# FMC_connector.net
KiCad netlist of a schematic drawn in Altium Designer
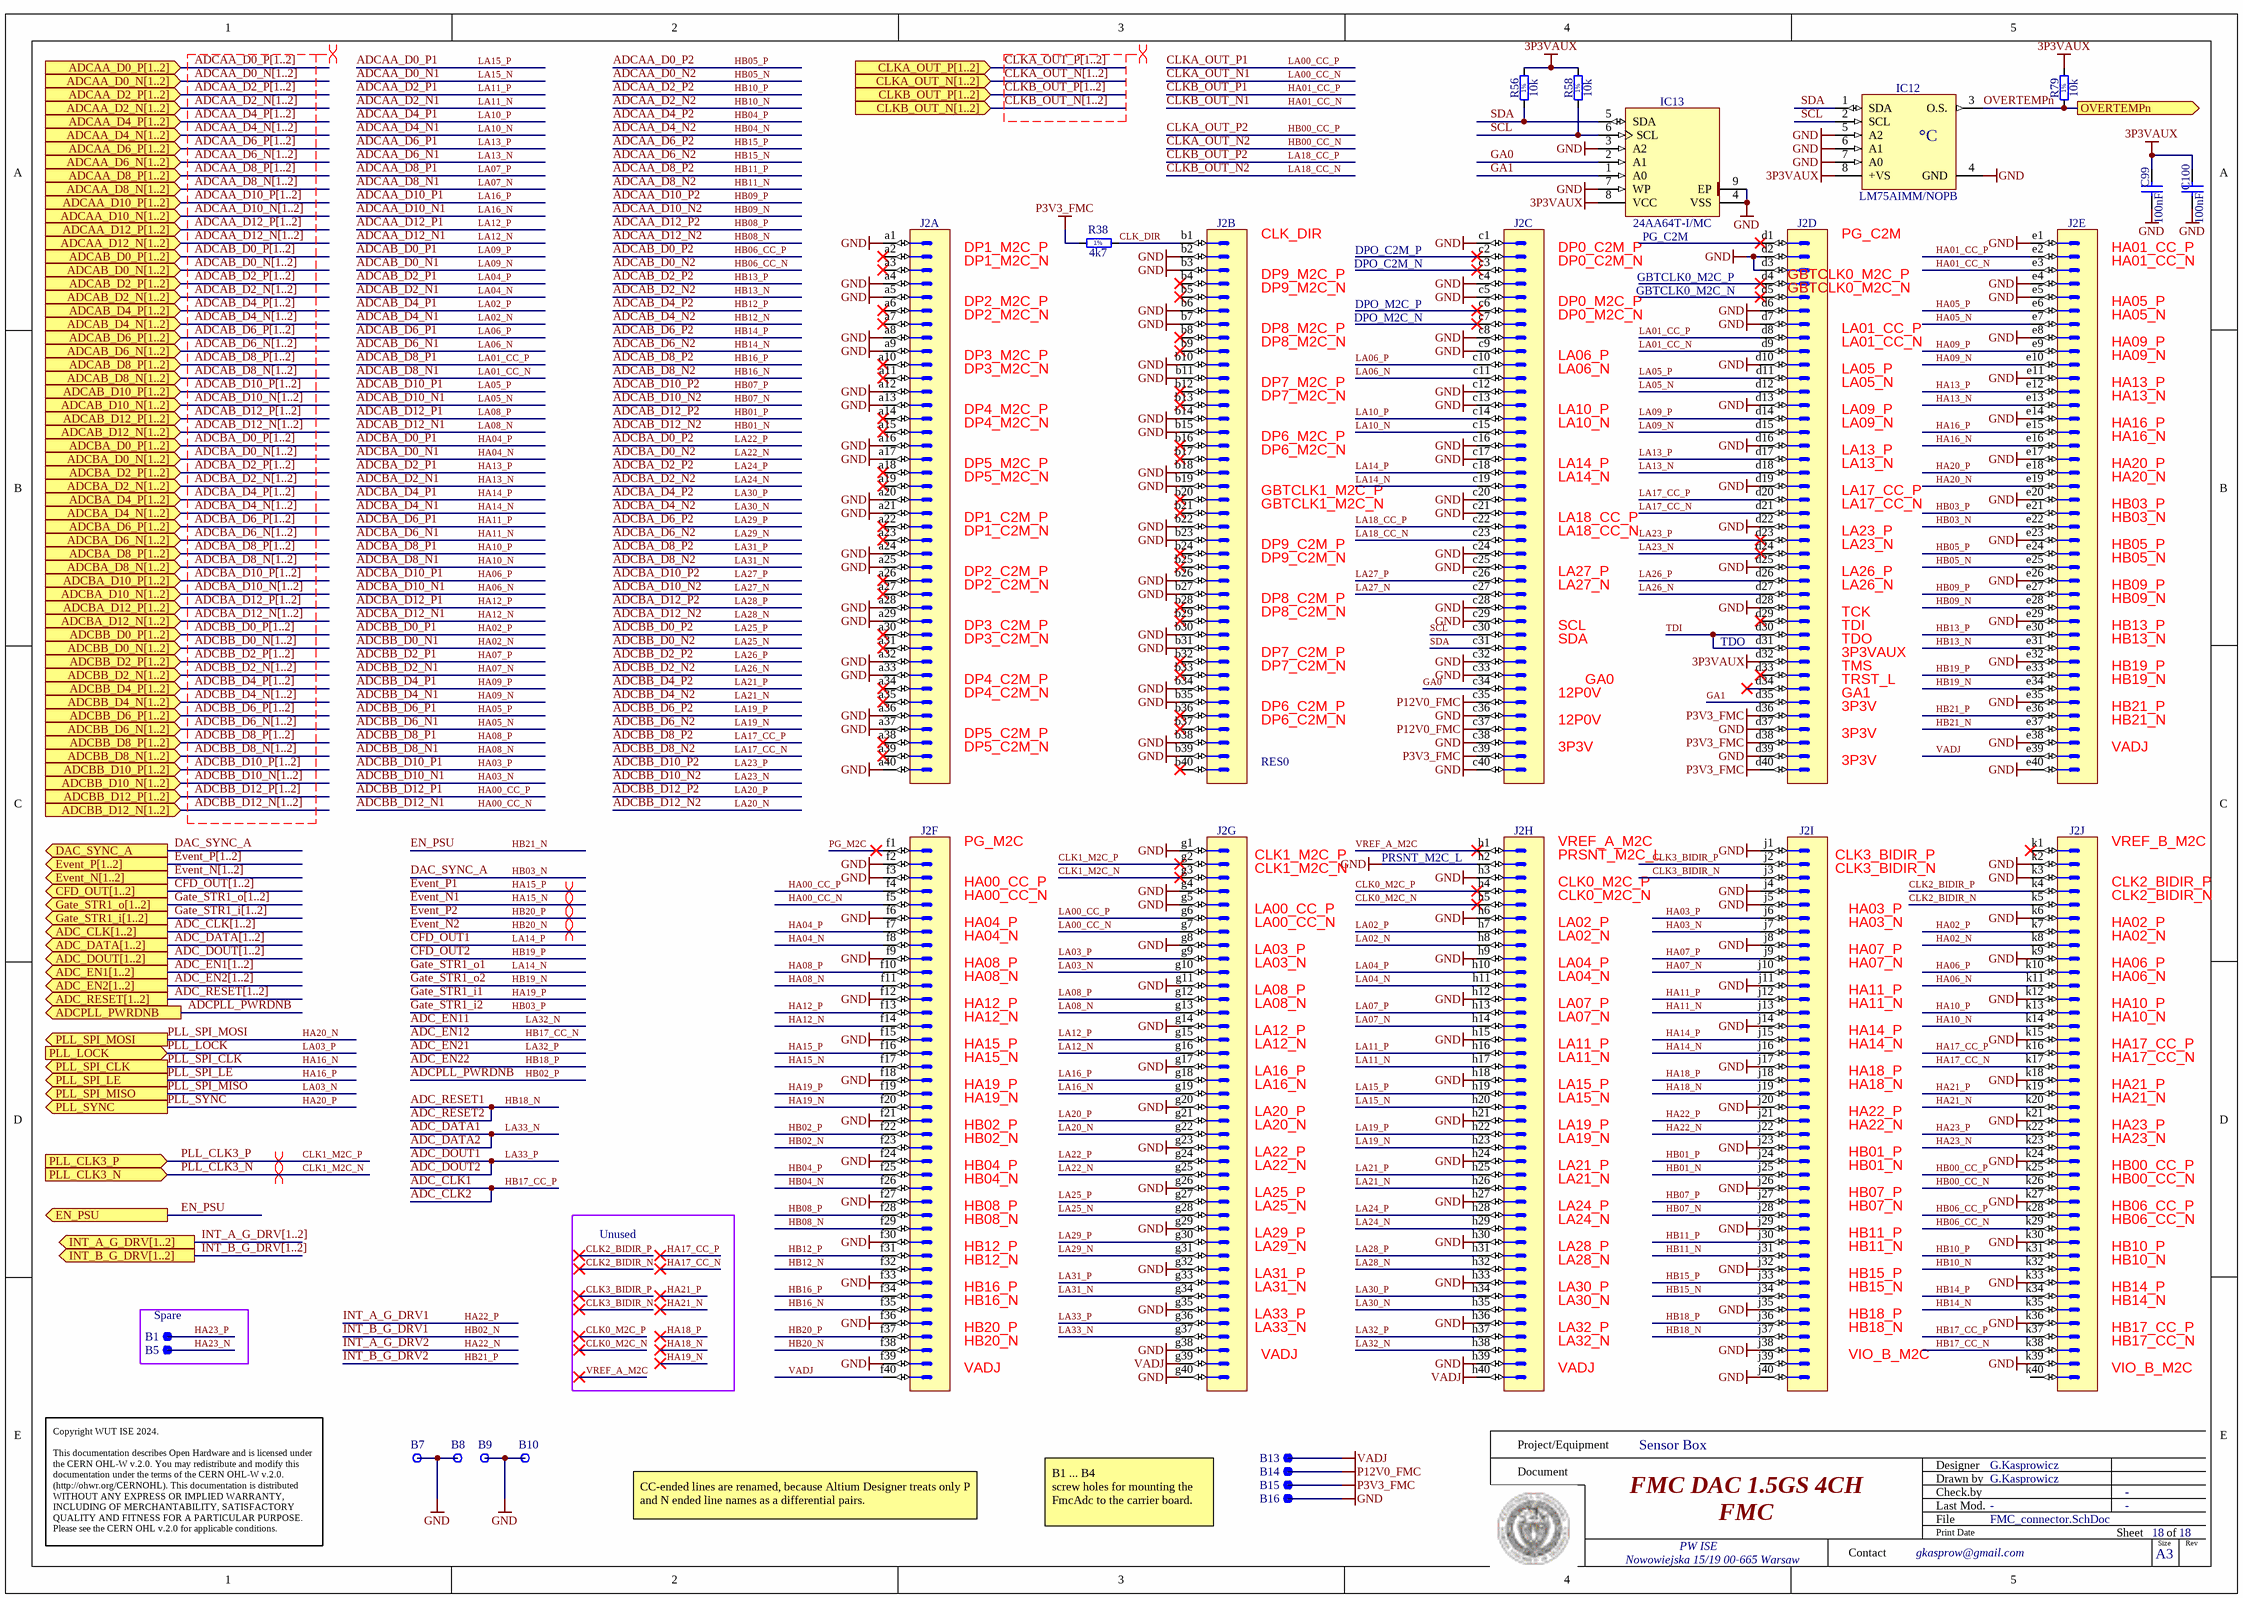
[diagram p0: FMC_connector.SchDoc]

(export (version "E")
  (design (tool "Eeschema 10.0.6"))
  (components
    (comp (ref "B1")
      (value "SMD Pad")
      (footprint "C100")
      (description "Pad")
      (fields (field (name "PART NUMBER") "SMD_PAD_D1MM") (field (name "AUTHOR") "CERN DEM JLC"))
      (libsource (lib "Eletro-mechanical") (part "Single SMD Pad (Round)"))
    )
    (comp (ref "B5")
      (value "SMD Pad")
      (footprint "C100")
      (description "Pad")
      (fields (field (name "PART NUMBER") "SMD_PAD_D1MM") (field (name "AUTHOR") "CERN DEM JLC"))
      (libsource (lib "Eletro-mechanical") (part "Single SMD Pad (Round)"))
    )
    (comp (ref "B7")
      (value "Plated Hole")
      (footprint "MTG300_600")
      (description "Single Terminal Socket")
      (fields (field (name "PART NUMBER") "PLATED_HOLE3.0_PAD6.0") (field (name "AUTHOR") "CERN DEM JLC"))
      (libsource (lib "Eletro-mechanical") (part "Single Terminal Socket"))
    )
    (comp (ref "B8")
      (value "Plated Hole")
      (footprint "MTG300_600")
      (description "Single Terminal Socket")
      (fields (field (name "PART NUMBER") "PLATED_HOLE3.0_PAD6.0") (field (name "AUTHOR") "CERN DEM JLC"))
      (libsource (lib "Eletro-mechanical") (part "Single Terminal Socket"))
    )
    (comp (ref "B9")
      (value "Plated Hole")
      (footprint "MTG300_600")
      (description "Single Terminal Socket")
      (fields (field (name "PART NUMBER") "PLATED_HOLE3.0_PAD6.0") (field (name "AUTHOR") "CERN DEM JLC"))
      (libsource (lib "Eletro-mechanical") (part "Single Terminal Socket"))
    )
    (comp (ref "B10")
      (value "Plated Hole")
      (footprint "MTG300_600")
      (description "Single Terminal Socket")
      (fields (field (name "PART NUMBER") "PLATED_HOLE3.0_PAD6.0") (field (name "AUTHOR") "CERN DEM JLC"))
      (libsource (lib "Eletro-mechanical") (part "Single Terminal Socket"))
    )
    (comp (ref "B13")
      (value "SMD Pad")
      (footprint "C100")
      (description "Pad")
      (fields (field (name "PART NUMBER") "SMD_PAD_D1MM") (field (name "AUTHOR") "CERN DEM JLC"))
      (libsource (lib "Eletro-mechanical") (part "Single SMD Pad (Round)"))
    )
    (comp (ref "B14")
      (value "SMD Pad")
      (footprint "C100")
      (description "Pad")
      (fields (field (name "PART NUMBER") "SMD_PAD_D1MM") (field (name "AUTHOR") "CERN DEM JLC"))
      (libsource (lib "Eletro-mechanical") (part "Single SMD Pad (Round)"))
    )
    (comp (ref "B15")
      (value "SMD Pad")
      (footprint "C100")
      (description "Pad")
      (fields (field (name "PART NUMBER") "SMD_PAD_D1MM") (field (name "AUTHOR") "CERN DEM JLC"))
      (libsource (lib "Eletro-mechanical") (part "Single SMD Pad (Round)"))
    )
    (comp (ref "B16")
      (value "SMD Pad")
      (footprint "C100")
      (description "Pad")
      (fields (field (name "PART NUMBER") "SMD_PAD_D1MM") (field (name "AUTHOR") "CERN DEM JLC"))
      (libsource (lib "Eletro-mechanical") (part "Single SMD Pad (Round)"))
    )
    (comp (ref "C99")
      (value "100nF")
      (footprint "CAPC1005X55N")
      (description "Non-polarised capacitor")
      (fields
        (field (name "PART NUMBER") "CC0402_100NF_16V_10%_X5R")
        (field (name "VOLTAGE") "16V")
        (field (name "AUTHOR") "CERN DEM JLC")
      )
      (libsource (lib "Capacitors") (part "Capacitor - non polarized"))
    )
    (comp (ref "C100")
      (value "100nF")
      (footprint "CAPC1005X55N")
      (description "Non-polarised capacitor")
      (fields
        (field (name "PART NUMBER") "CC0402_100NF_16V_10%_X5R")
        (field (name "VOLTAGE") "16V")
        (field (name "AUTHOR") "CERN DEM JLC")
      )
      (libsource (lib "Capacitors") (part "Capacitor - non polarized"))
    )
    (comp (ref "IC12")
      (value "LM75AIMM/NOPB")
      (footprint "SOP65P490X109-8N")
      (description "Digital Temperature Sensor and Thermal Watchdog with Two-Wire Interface")
      (fields (field (name "MANUFACTURER") "TEXAS INSTRUMENTS") (field (name "AUTHOR") "CERN DEM JLC"))
      (libsource (lib "ICs And Semiconductors") (part "LM75"))
    )
    (comp (ref "IC13")
      (value "24AA64T-I/MC")
      (footprint "SON50P300X200X100-9N-R175X155")
      (description "1.7V-5.5V 64K I2C Serial EEPROM")
      (fields (field (name "MANUFACTURER") "MICROCHIP TECHNOLOGY") (field (name "AUTHOR") "CERN DEM JLC"))
      (libsource (lib "ICs And Semiconductors") (part "24AA64T-I/MC"))
    )
    (comp (ref "J2")
      (value "VITA 57")
      (footprint "SAMTEC_ASP-134488-01")
      (description "Connector VITA 57, 400 Male contacts in 10 row abcdefghj")
      (fields
        (field (name "PART NUMBER") "SAMTEC_ASP-134488-01")
        (field (name "MANUFACTURER") "SAMTEC")
        (field (name "AUTHOR") "CERN DEM JLC")
      )
      (libsource (lib "Connectors") (part "Connector VITA 57 400 Male (abcdefghjk)"))
    )
    (comp (ref "R38")
      (value "4k7")
      (footprint "RESC1608X55N")
      (description "Resistor - 1%")
      (fields
        (field (name "PART NUMBER") "R0603_4K7_1%_0.1W_100PPM")
        (field (name "POWER") "0.1W")
        (field (name "AUTHOR") "CERN DEM JLC")
      )
      (libsource (lib "Resistors") (part "Resistor - 1%"))
    )
    (comp (ref "R56")
      (value "10k")
      (footprint "RESC1005X40N")
      (description "Resistor - 1%")
      (fields
        (field (name "PART NUMBER") "R0402_10K_1%_0.0625W_100PPM")
        (field (name "POWER") "0.0625W")
        (field (name "AUTHOR") "CERN DEM JLC")
      )
      (libsource (lib "Resistors") (part "Resistor - 1%"))
    )
    (comp (ref "R58")
      (value "10k")
      (footprint "RESC1005X40N")
      (description "Resistor - 1%")
      (fields
        (field (name "PART NUMBER") "R0402_10K_1%_0.0625W_100PPM")
        (field (name "POWER") "0.0625W")
        (field (name "AUTHOR") "CERN DEM JLC")
      )
      (libsource (lib "Resistors") (part "Resistor - 1%"))
    )
    (comp (ref "R79")
      (value "10k")
      (footprint "RESC1005X40N")
      (description "Resistor - 1%")
      (fields
        (field (name "PART NUMBER") "R0402_10K_1%_0.0625W_100PPM")
        (field (name "POWER") "0.0625W")
        (field (name "AUTHOR") "CERN DEM JLC")
      )
      (libsource (lib "Resistors") (part "Resistor - 1%"))
    )
  )
  (nets
    (net (code "1") (name "/ADCAA_D0_N1") (class "Default")
      (node (ref "J2") (pin "h20") (pinfunction "h20_h20") (pintype "bidirectional"))
    )
    (net (code "2") (name "/ADCAA_D0_N2") (class "Default")
      (node (ref "J2") (pin "e25") (pinfunction "e25_e25") (pintype "bidirectional"))
    )
    (net (code "4") (name "/ADCAA_D0_P1") (class "Default")
      (node (ref "J2") (pin "h19") (pinfunction "h19_h19") (pintype "bidirectional"))
    )
    (net (code "5") (name "/ADCAA_D0_P2") (class "Default")
      (node (ref "J2") (pin "e24") (pinfunction "e24_e24") (pintype "bidirectional"))
    )
    (net (code "7") (name "/ADCAA_D2_N1") (class "Default")
      (node (ref "J2") (pin "h17") (pinfunction "h17_h17") (pintype "bidirectional"))
    )
    (net (code "8") (name "/ADCAA_D2_N2") (class "Default")
      (node (ref "J2") (pin "k32") (pinfunction "k32_k32") (pintype "bidirectional"))
    )
    (net (code "10") (name "/ADCAA_D2_P1") (class "Default")
      (node (ref "J2") (pin "h16") (pinfunction "h16_h16") (pintype "bidirectional"))
    )
    (net (code "11") (name "/ADCAA_D2_P2") (class "Default")
      (node (ref "J2") (pin "k31") (pinfunction "k31_k31") (pintype "bidirectional"))
    )
    (net (code "13") (name "/ADCAA_D4_N1") (class "Default")
      (node (ref "J2") (pin "c15") (pinfunction "c15_c15") (pintype "bidirectional"))
    )
    (net (code "14") (name "/ADCAA_D4_N2") (class "Default")
      (node (ref "J2") (pin "f26") (pinfunction "f26_f26") (pintype "bidirectional"))
    )
    (net (code "16") (name "/ADCAA_D4_P1") (class "Default")
      (node (ref "J2") (pin "c14") (pinfunction "c14_c14") (pintype "bidirectional"))
    )
    (net (code "17") (name "/ADCAA_D4_P2") (class "Default")
      (node (ref "J2") (pin "f25") (pinfunction "f25_f25") (pintype "bidirectional"))
    )
    (net (code "19") (name "/ADCAA_D6_N1") (class "Default")
      (node (ref "J2") (pin "d18") (pinfunction "d18_d18") (pintype "bidirectional"))
    )
    (net (code "20") (name "/ADCAA_D6_N2") (class "Default")
      (node (ref "J2") (pin "j34") (pinfunction "j34_j34") (pintype "bidirectional"))
    )
    (net (code "22") (name "/ADCAA_D6_P1") (class "Default")
      (node (ref "J2") (pin "d17") (pinfunction "d17_d17") (pintype "bidirectional"))
    )
    (net (code "23") (name "/ADCAA_D6_P2") (class "Default")
      (node (ref "J2") (pin "j33") (pinfunction "j33_j33") (pintype "bidirectional"))
    )
    (net (code "25") (name "/ADCAA_D8_N1") (class "Default")
      (node (ref "J2") (pin "h14") (pinfunction "h14_h14") (pintype "bidirectional"))
    )
    (net (code "26") (name "/ADCAA_D8_N2") (class "Default")
      (node (ref "J2") (pin "j31") (pinfunction "j31_j31") (pintype "bidirectional"))
    )
    (net (code "28") (name "/ADCAA_D8_P1") (class "Default")
      (node (ref "J2") (pin "h13") (pinfunction "h13_h13") (pintype "bidirectional"))
    )
    (net (code "29") (name "/ADCAA_D8_P2") (class "Default")
      (node (ref "J2") (pin "j30") (pinfunction "j30_j30") (pintype "bidirectional"))
    )
    (net (code "31") (name "/ADCAA_D10_N1") (class "Default")
      (node (ref "J2") (pin "g19") (pinfunction "g19_g19") (pintype "bidirectional"))
    )
    (net (code "32") (name "/ADCAA_D10_N2") (class "Default")
      (node (ref "J2") (pin "e28") (pinfunction "e28_e28") (pintype "bidirectional"))
    )
    (net (code "34") (name "/ADCAA_D10_P1") (class "Default")
      (node (ref "J2") (pin "g18") (pinfunction "g18_g18") (pintype "bidirectional"))
    )
    (net (code "35") (name "/ADCAA_D10_P2") (class "Default")
      (node (ref "J2") (pin "e27") (pinfunction "e27_e27") (pintype "bidirectional"))
    )
    (net (code "37") (name "/ADCAA_D12_N1") (class "Default")
      (node (ref "J2") (pin "g16") (pinfunction "g16_g16") (pintype "bidirectional"))
    )
    (net (code "38") (name "/ADCAA_D12_N2") (class "Default")
      (node (ref "J2") (pin "f29") (pinfunction "f29_f29") (pintype "bidirectional"))
    )
    (net (code "40") (name "/ADCAA_D12_P1") (class "Default")
      (node (ref "J2") (pin "g15") (pinfunction "g15_g15") (pintype "bidirectional"))
    )
    (net (code "41") (name "/ADCAA_D12_P2") (class "Default")
      (node (ref "J2") (pin "f28") (pinfunction "f28_f28") (pintype "bidirectional"))
    )
    (net (code "43") (name "/ADCAB_D0_N1") (class "Default")
      (node (ref "J2") (pin "d15") (pinfunction "d15_d15") (pintype "bidirectional"))
    )
    (net (code "44") (name "/ADCAB_D0_N2") (class "Default")
      (node (ref "J2") (pin "k29") (pinfunction "k29_k29") (pintype "bidirectional"))
    )
    (net (code "46") (name "/ADCAB_D0_P1") (class "Default")
      (node (ref "J2") (pin "d14") (pinfunction "d14_d14") (pintype "bidirectional"))
    )
    (net (code "47") (name "/ADCAB_D0_P2") (class "Default")
      (node (ref "J2") (pin "k28") (pinfunction "k28_k28") (pintype "bidirectional"))
    )
    (net (code "49") (name "/ADCAB_D2_N1") (class "Default")
      (node (ref "J2") (pin "h11") (pinfunction "h11_h11") (pintype "bidirectional"))
    )
    (net (code "50") (name "/ADCAB_D2_N2") (class "Default")
      (node (ref "J2") (pin "e31") (pinfunction "e31_e31") (pintype "bidirectional"))
    )
    (net (code "52") (name "/ADCAB_D2_P1") (class "Default")
      (node (ref "J2") (pin "h10") (pinfunction "h10_h10") (pintype "bidirectional"))
    )
    (net (code "53") (name "/ADCAB_D2_P2") (class "Default")
      (node (ref "J2") (pin "e30") (pinfunction "e30_e30") (pintype "bidirectional"))
    )
    (net (code "55") (name "/ADCAB_D4_N1") (class "Default")
      (node (ref "J2") (pin "h8") (pinfunction "h8_h8") (pintype "bidirectional"))
    )
    (net (code "56") (name "/ADCAB_D4_N2") (class "Default")
      (node (ref "J2") (pin "f32") (pinfunction "f32_f32") (pintype "bidirectional"))
    )
    (net (code "58") (name "/ADCAB_D4_P1") (class "Default")
      (node (ref "J2") (pin "h7") (pinfunction "h7_h7") (pintype "bidirectional"))
    )
    (net (code "59") (name "/ADCAB_D4_P2") (class "Default")
      (node (ref "J2") (pin "f31") (pinfunction "f31_f31") (pintype "bidirectional"))
    )
    (net (code "61") (name "/ADCAB_D6_N1") (class "Default")
      (node (ref "J2") (pin "c11") (pinfunction "c11_c11") (pintype "bidirectional"))
    )
    (net (code "62") (name "/ADCAB_D6_N2") (class "Default")
      (node (ref "J2") (pin "k35") (pinfunction "k35_k35") (pintype "bidirectional"))
    )
    (net (code "64") (name "/ADCAB_D6_P1") (class "Default")
      (node (ref "J2") (pin "c10") (pinfunction "c10_c10") (pintype "bidirectional"))
    )
    (net (code "65") (name "/ADCAB_D6_P2") (class "Default")
      (node (ref "J2") (pin "k34") (pinfunction "k34_k34") (pintype "bidirectional"))
    )
    (net (code "67") (name "/ADCAB_D8_N1") (class "Default")
      (node (ref "J2") (pin "d9") (pinfunction "d9_d9") (pintype "bidirectional"))
    )
    (net (code "68") (name "/ADCAB_D8_N2") (class "Default")
      (node (ref "J2") (pin "f35") (pinfunction "f35_f35") (pintype "bidirectional"))
    )
    (net (code "70") (name "/ADCAB_D8_P1") (class "Default")
      (node (ref "J2") (pin "d8") (pinfunction "d8_d8") (pintype "bidirectional"))
    )
    (net (code "71") (name "/ADCAB_D8_P2") (class "Default")
      (node (ref "J2") (pin "f34") (pinfunction "f34_f34") (pintype "bidirectional"))
    )
    (net (code "73") (name "/ADCAB_D10_N1") (class "Default")
      (node (ref "J2") (pin "d12") (pinfunction "d12_d12") (pintype "bidirectional"))
    )
    (net (code "74") (name "/ADCAB_D10_N2") (class "Default")
      (node (ref "J2") (pin "j28") (pinfunction "j28_j28") (pintype "bidirectional"))
    )
    (net (code "76") (name "/ADCAB_D10_P1") (class "Default")
      (node (ref "J2") (pin "d11") (pinfunction "d11_d11") (pintype "bidirectional"))
    )
    (net (code "77") (name "/ADCAB_D10_P2") (class "Default")
      (node (ref "J2") (pin "j27") (pinfunction "j27_j27") (pintype "bidirectional"))
    )
    (net (code "79") (name "/ADCAB_D12_N1") (class "Default")
      (node (ref "J2") (pin "g13") (pinfunction "g13_g13") (pintype "bidirectional"))
    )
    (net (code "80") (name "/ADCAB_D12_N2") (class "Default")
      (node (ref "J2") (pin "j25") (pinfunction "j25_j25") (pintype "bidirectional"))
    )
    (net (code "82") (name "/ADCAB_D12_P1") (class "Default")
      (node (ref "J2") (pin "g12") (pinfunction "g12_g12") (pintype "bidirectional"))
    )
    (net (code "83") (name "/ADCAB_D12_P2") (class "Default")
      (node (ref "J2") (pin "j24") (pinfunction "j24_j24") (pintype "bidirectional"))
    )
    (net (code "85") (name "/ADCBA_D0_N1") (class "Default")
      (node (ref "J2") (pin "f8") (pinfunction "f8_f8") (pintype "bidirectional"))
    )
    (net (code "86") (name "/ADCBA_D0_N2") (class "Default")
      (node (ref "J2") (pin "g25") (pinfunction "g25_g25") (pintype "bidirectional"))
    )
    (net (code "88") (name "/ADCBA_D0_P1") (class "Default")
      (node (ref "J2") (pin "f7") (pinfunction "f7_f7") (pintype "bidirectional"))
    )
    (net (code "89") (name "/ADCBA_D0_P2") (class "Default")
      (node (ref "J2") (pin "g24") (pinfunction "g24_g24") (pintype "bidirectional"))
    )
    (net (code "91") (name "/ADCBA_D2_N1") (class "Default")
      (node (ref "J2") (pin "e13") (pinfunction "e13_e13") (pintype "bidirectional"))
    )
    (net (code "92") (name "/ADCBA_D2_N2") (class "Default")
      (node (ref "J2") (pin "h29") (pinfunction "h29_h29") (pintype "bidirectional"))
    )
    (net (code "94") (name "/ADCBA_D2_P1") (class "Default")
      (node (ref "J2") (pin "e12") (pinfunction "e12_e12") (pintype "bidirectional"))
    )
    (net (code "95") (name "/ADCBA_D2_P2") (class "Default")
      (node (ref "J2") (pin "h28") (pinfunction "h28_h28") (pintype "bidirectional"))
    )
    (net (code "97") (name "/ADCBA_D4_N1") (class "Default")
      (node (ref "J2") (pin "j16") (pinfunction "j16_j16") (pintype "bidirectional"))
    )
    (net (code "98") (name "/ADCBA_D4_N2") (class "Default")
      (node (ref "J2") (pin "h35") (pinfunction "h35_h35") (pintype "bidirectional"))
    )
    (net (code "100") (name "/ADCBA_D4_P1") (class "Default")
      (node (ref "J2") (pin "j15") (pinfunction "j15_j15") (pintype "bidirectional"))
    )
    (net (code "101") (name "/ADCBA_D4_P2") (class "Default")
      (node (ref "J2") (pin "h34") (pinfunction "h34_h34") (pintype "bidirectional"))
    )
    (net (code "103") (name "/ADCBA_D6_N1") (class "Default")
      (node (ref "J2") (pin "j13") (pinfunction "j13_j13") (pintype "bidirectional"))
    )
    (net (code "104") (name "/ADCBA_D6_N2") (class "Default")
      (node (ref "J2") (pin "g31") (pinfunction "g31_g31") (pintype "bidirectional"))
    )
    (net (code "106") (name "/ADCBA_D6_P1") (class "Default")
      (node (ref "J2") (pin "j12") (pinfunction "j12_j12") (pintype "bidirectional"))
    )
    (net (code "107") (name "/ADCBA_D6_P2") (class "Default")
      (node (ref "J2") (pin "g30") (pinfunction "g30_g30") (pintype "bidirectional"))
    )
    (net (code "109") (name "/ADCBA_D8_N1") (class "Default")
      (node (ref "J2") (pin "k14") (pinfunction "k14_k14") (pintype "bidirectional"))
    )
    (net (code "110") (name "/ADCBA_D8_N2") (class "Default")
      (node (ref "J2") (pin "g34") (pinfunction "g34_g34") (pintype "bidirectional"))
    )
    (net (code "112") (name "/ADCBA_D8_P1") (class "Default")
      (node (ref "J2") (pin "k13") (pinfunction "k13_k13") (pintype "bidirectional"))
    )
    (net (code "113") (name "/ADCBA_D8_P2") (class "Default")
      (node (ref "J2") (pin "g33") (pinfunction "g33_g33") (pintype "bidirectional"))
    )
    (net (code "115") (name "/ADCBA_D10_N1") (class "Default")
      (node (ref "J2") (pin "k11") (pinfunction "k11_k11") (pintype "bidirectional"))
    )
    (net (code "116") (name "/ADCBA_D10_N2") (class "Default")
      (node (ref "J2") (pin "c27") (pinfunction "c27_c27") (pintype "bidirectional"))
    )
    (net (code "118") (name "/ADCBA_D10_P1") (class "Default")
      (node (ref "J2") (pin "k10") (pinfunction "k10_k10") (pintype "bidirectional"))
    )
    (net (code "119") (name "/ADCBA_D10_P2") (class "Default")
      (node (ref "J2") (pin "c26") (pinfunction "c26_c26") (pintype "bidirectional"))
    )
    (net (code "121") (name "/ADCBA_D12_N1") (class "Default")
      (node (ref "J2") (pin "f14") (pinfunction "f14_f14") (pintype "bidirectional"))
    )
    (net (code "122") (name "/ADCBA_D12_N2") (class "Default")
      (node (ref "J2") (pin "h32") (pinfunction "h32_h32") (pintype "bidirectional"))
    )
    (net (code "124") (name "/ADCBA_D12_P1") (class "Default")
      (node (ref "J2") (pin "f13") (pinfunction "f13_f13") (pintype "bidirectional"))
    )
    (net (code "125") (name "/ADCBA_D12_P2") (class "Default")
      (node (ref "J2") (pin "h31") (pinfunction "h31_h31") (pintype "bidirectional"))
    )
    (net (code "127") (name "/ADCBB_D0_N1") (class "Default")
      (node (ref "J2") (pin "k8") (pinfunction "k8_k8") (pintype "bidirectional"))
    )
    (net (code "128") (name "/ADCBB_D0_N2") (class "Default")
      (node (ref "J2") (pin "g28") (pinfunction "g28_g28") (pintype "bidirectional"))
    )
    (net (code "130") (name "/ADCBB_D0_P1") (class "Default")
      (node (ref "J2") (pin "k7") (pinfunction "k7_k7") (pintype "bidirectional"))
    )
    (net (code "131") (name "/ADCBB_D0_P2") (class "Default")
      (node (ref "J2") (pin "g27") (pinfunction "g27_g27") (pintype "bidirectional"))
    )
    (net (code "133") (name "/ADCBB_D2_N1") (class "Default")
      (node (ref "J2") (pin "j10") (pinfunction "j10_j10") (pintype "bidirectional"))
    )
    (net (code "134") (name "/ADCBB_D2_N2") (class "Default")
      (node (ref "J2") (pin "d27") (pinfunction "d27_d27") (pintype "bidirectional"))
    )
    (net (code "136") (name "/ADCBB_D2_P1") (class "Default")
      (node (ref "J2") (pin "j9") (pinfunction "j9_j9") (pintype "bidirectional"))
    )
    (net (code "137") (name "/ADCBB_D2_P2") (class "Default")
      (node (ref "J2") (pin "d26") (pinfunction "d26_d26") (pintype "bidirectional"))
    )
    (net (code "139") (name "/ADCBB_D4_N1") (class "Default")
      (node (ref "J2") (pin "e10") (pinfunction "e10_e10") (pintype "bidirectional"))
    )
    (net (code "140") (name "/ADCBB_D4_N2") (class "Default")
      (node (ref "J2") (pin "h26") (pinfunction "h26_h26") (pintype "bidirectional"))
    )
    (net (code "142") (name "/ADCBB_D4_P1") (class "Default")
      (node (ref "J2") (pin "e9") (pinfunction "e9_e9") (pintype "bidirectional"))
    )
    (net (code "143") (name "/ADCBB_D4_P2") (class "Default")
      (node (ref "J2") (pin "h25") (pinfunction "h25_h25") (pintype "bidirectional"))
    )
    (net (code "145") (name "/ADCBB_D6_N1") (class "Default")
      (node (ref "J2") (pin "e7") (pinfunction "e7_e7") (pintype "bidirectional"))
    )
    (net (code "146") (name "/ADCBB_D6_N2") (class "Default")
      (node (ref "J2") (pin "h23") (pinfunction "h23_h23") (pintype "bidirectional"))
    )
    (net (code "148") (name "/ADCBB_D6_P1") (class "Default")
      (node (ref "J2") (pin "e6") (pinfunction "e6_e6") (pintype "bidirectional"))
    )
    (net (code "149") (name "/ADCBB_D6_P2") (class "Default")
      (node (ref "J2") (pin "h22") (pinfunction "h22_h22") (pintype "bidirectional"))
    )
    (net (code "151") (name "/ADCBB_D8_N1") (class "Default")
      (node (ref "J2") (pin "f11") (pinfunction "f11_f11") (pintype "bidirectional"))
    )
    (net (code "152") (name "/ADCBB_D8_N2") (class "Default")
      (node (ref "J2") (pin "d21") (pinfunction "d21_d21") (pintype "bidirectional"))
    )
    (net (code "154") (name "/ADCBB_D8_P1") (class "Default")
      (node (ref "J2") (pin "f10") (pinfunction "f10_f10") (pintype "bidirectional"))
    )
    (net (code "155") (name "/ADCBB_D8_P2") (class "Default")
      (node (ref "J2") (pin "d20") (pinfunction "d20_d20") (pintype "bidirectional"))
    )
    (net (code "157") (name "/ADCBB_D10_N1") (class "Default")
      (node (ref "J2") (pin "j7") (pinfunction "j7_j7") (pintype "bidirectional"))
    )
    (net (code "158") (name "/ADCBB_D10_N2") (class "Default")
      (node (ref "J2") (pin "d24") (pinfunction "d24_d24") (pintype "bidirectional"))
    )
    (net (code "160") (name "/ADCBB_D10_P1") (class "Default")
      (node (ref "J2") (pin "j6") (pinfunction "j6_j6") (pintype "bidirectional"))
    )
    (net (code "161") (name "/ADCBB_D10_P2") (class "Default")
      (node (ref "J2") (pin "d23") (pinfunction "d23_d23") (pintype "bidirectional"))
    )
    (net (code "163") (name "/ADCBB_D12_N1") (class "Default")
      (node (ref "J2") (pin "f5") (pinfunction "f5_f5") (pintype "bidirectional"))
    )
    (net (code "164") (name "/ADCBB_D12_N2") (class "Default")
      (node (ref "J2") (pin "g22") (pinfunction "g22_g22") (pintype "bidirectional"))
    )
    (net (code "166") (name "/ADCBB_D12_P1") (class "Default")
      (node (ref "J2") (pin "f4") (pinfunction "f4_f4") (pintype "bidirectional"))
    )
    (net (code "167") (name "/ADCBB_D12_P2") (class "Default")
      (node (ref "J2") (pin "g21") (pinfunction "g21_g21") (pintype "bidirectional"))
    )
    (net (code "169") (name "/ADCPLL_PWRDNB") (class "Default")
      (node (ref "J2") (pin "f22") (pinfunction "f22_f22") (pintype "bidirectional"))
    )
    (net (code "170") (name "/ADC_CLK2") (class "Default")
      (node (ref "J2") (pin "k37") (pinfunction "k37_k37") (pintype "bidirectional"))
    )
    (net (code "172") (name "/ADC_DATA2") (class "Default")
      (node (ref "J2") (pin "g37") (pinfunction "g37_g37") (pintype "bidirectional"))
    )
    (net (code "174") (name "/ADC_DOUT2") (class "Default")
      (node (ref "J2") (pin "g36") (pinfunction "g36_g36") (pintype "bidirectional"))
    )
    (net (code "178") (name "/ADC_EN11") (class "Default")
      (node (ref "J2") (pin "h38") (pinfunction "h38_h38") (pintype "bidirectional"))
    )
    (net (code "179") (name "/ADC_EN12") (class "Default")
      (node (ref "J2") (pin "k38") (pinfunction "k38_k38") (pintype "bidirectional"))
    )
    (net (code "180") (name "/ADC_EN21") (class "Default")
      (node (ref "J2") (pin "h37") (pinfunction "h37_h37") (pintype "bidirectional"))
    )
    (net (code "181") (name "/ADC_EN22") (class "Default")
      (node (ref "J2") (pin "j36") (pinfunction "j36_j36") (pintype "bidirectional"))
    )
    (net (code "182") (name "/ADC_RESET2") (class "Default")
      (node (ref "J2") (pin "j37") (pinfunction "j37_j37") (pintype "bidirectional"))
    )
    (net (code "184") (name "/CFD_OUT1") (class "Default")
      (node (ref "J2") (pin "c18") (pinfunction "c18_c18") (pintype "bidirectional"))
    )
    (net (code "185") (name "/CFD_OUT2") (class "Default")
      (node (ref "J2") (pin "e33") (pinfunction "e33_e33") (pintype "bidirectional"))
    )
    (net (code "187") (name "/CLK0_M2C_N") (class "Default")
      (node (ref "J2") (pin "h5") (pinfunction "h5_h5") (pintype "bidirectional+no_connect"))
    )
    (net (code "188") (name "/CLK0_M2C_P") (class "Default")
      (node (ref "J2") (pin "h4") (pinfunction "h4_h4") (pintype "bidirectional+no_connect"))
    )
    (net (code "189") (name "/CLK1_M2C_N") (class "Default")
      (node (ref "J2") (pin "g3") (pinfunction "g3_g3") (pintype "bidirectional+no_connect"))
    )
    (net (code "190") (name "/CLK1_M2C_P") (class "Default")
      (node (ref "J2") (pin "g2") (pinfunction "g2_g2") (pintype "bidirectional+no_connect"))
    )
    (net (code "191") (name "/CLK2_BIDIR_N") (class "Default")
      (node (ref "J2") (pin "k5") (pinfunction "k5_k5") (pintype "bidirectional"))
    )
    (net (code "192") (name "/CLK2_BIDIR_P") (class "Default")
      (node (ref "J2") (pin "k4") (pinfunction "k4_k4") (pintype "bidirectional"))
    )
    (net (code "193") (name "/CLK3_BIDIR_N") (class "Default")
      (node (ref "J2") (pin "j3") (pinfunction "j3_j3") (pintype "bidirectional"))
    )
    (net (code "194") (name "/CLK3_BIDIR_P") (class "Default")
      (node (ref "J2") (pin "j2") (pinfunction "j2_j2") (pintype "bidirectional"))
    )
    (net (code "195") (name "/CLKA_OUT_N1") (class "Default")
      (node (ref "J2") (pin "g7") (pinfunction "g7_g7") (pintype "bidirectional"))
    )
    (net (code "196") (name "/CLKA_OUT_N2") (class "Default")
      (node (ref "J2") (pin "k26") (pinfunction "k26_k26") (pintype "bidirectional"))
    )
    (net (code "198") (name "/CLKA_OUT_P1") (class "Default")
      (node (ref "J2") (pin "g6") (pinfunction "g6_g6") (pintype "bidirectional"))
    )
    (net (code "199") (name "/CLKA_OUT_P2") (class "Default")
      (node (ref "J2") (pin "k25") (pinfunction "k25_k25") (pintype "bidirectional"))
    )
    (net (code "201") (name "/CLKB_OUT_N1") (class "Default")
      (node (ref "J2") (pin "e3") (pinfunction "e3_e3") (pintype "bidirectional"))
    )
    (net (code "202") (name "/CLKB_OUT_N2") (class "Default")
      (node (ref "J2") (pin "c23") (pinfunction "c23_c23") (pintype "bidirectional"))
    )
    (net (code "204") (name "/CLKB_OUT_P1") (class "Default")
      (node (ref "J2") (pin "e2") (pinfunction "e2_e2") (pintype "bidirectional"))
    )
    (net (code "205") (name "/CLKB_OUT_P2") (class "Default")
      (node (ref "J2") (pin "c22") (pinfunction "c22_c22") (pintype "bidirectional"))
    )
    (net (code "207") (name "/CLK_DIR") (class "Default")
      (node (ref "J2") (pin "b1") (pinfunction "b1_b1") (pintype "bidirectional"))
      (node (ref "R38") (pin "2") (pinfunction "2_2") (pintype "passive"))
    )
    (net (code "208") (name "/DAC_SYNC_A") (class "Default")
      (node (ref "J2") (pin "e22") (pinfunction "e22_e22") (pintype "bidirectional"))
    )
    (net (code "209") (name "/EN_PSU") (class "Default")
      (node (ref "J2") (pin "e37") (pinfunction "e37_e37") (pintype "bidirectional"))
    )
    (net (code "210") (name "/Event_N1") (class "Default")
      (node (ref "J2") (pin "f17") (pinfunction "f17_f17") (pintype "bidirectional"))
    )
    (net (code "211") (name "/Event_N2") (class "Default")
      (node (ref "J2") (pin "f38") (pinfunction "f38_f38") (pintype "bidirectional"))
    )
    (net (code "213") (name "/Event_P1") (class "Default")
      (node (ref "J2") (pin "f16") (pinfunction "f16_f16") (pintype "bidirectional"))
    )
    (net (code "214") (name "/Event_P2") (class "Default")
      (node (ref "J2") (pin "f37") (pinfunction "f37_f37") (pintype "bidirectional"))
    )
    (net (code "216") (name "/GA0") (class "Default")
      (node (ref "IC13") (pin "2") (pinfunction "A1_2") (pintype "input"))
      (node (ref "J2") (pin "c34") (pinfunction "c34_c34") (pintype "bidirectional"))
    )
    (net (code "217") (name "/GA1") (class "Default")
      (node (ref "IC13") (pin "1") (pinfunction "A0_1") (pintype "input"))
      (node (ref "J2") (pin "d35") (pinfunction "d35_d35") (pintype "bidirectional"))
    )
    (net (code "218") (name "/Gate_STR1_i1") (class "Default")
      (node (ref "J2") (pin "f19") (pinfunction "f19_f19") (pintype "bidirectional"))
    )
    (net (code "219") (name "/Gate_STR1_i2") (class "Default")
      (node (ref "J2") (pin "e21") (pinfunction "e21_e21") (pintype "bidirectional"))
    )
    (net (code "221") (name "/Gate_STR1_o1") (class "Default")
      (node (ref "J2") (pin "c19") (pinfunction "c19_c19") (pintype "bidirectional"))
    )
    (net (code "222") (name "/Gate_STR1_o2") (class "Default")
      (node (ref "J2") (pin "e34") (pinfunction "e34_e34") (pintype "bidirectional"))
    )
    (net (code "224") (name "/HA16_N") (class "Default")
      (node (ref "J2") (pin "e16") (pinfunction "e16_e16") (pintype "bidirectional"))
    )
    (net (code "225") (name "/HA16_P") (class "Default")
      (node (ref "J2") (pin "e15") (pinfunction "e15_e15") (pintype "bidirectional"))
    )
    (net (code "226") (name "/HA17_CC_N") (class "Default")
      (node (ref "J2") (pin "k17") (pinfunction "k17_k17") (pintype "bidirectional"))
    )
    (net (code "227") (name "/HA17_CC_P") (class "Default")
      (node (ref "J2") (pin "k16") (pinfunction "k16_k16") (pintype "bidirectional"))
    )
    (net (code "228") (name "/HA18_N") (class "Default")
      (node (ref "J2") (pin "j19") (pinfunction "j19_j19") (pintype "bidirectional"))
    )
    (net (code "229") (name "/HA18_P") (class "Default")
      (node (ref "J2") (pin "j18") (pinfunction "j18_j18") (pintype "bidirectional"))
    )
    (net (code "230") (name "/HA19_N") (class "Default")
      (node (ref "J2") (pin "f20") (pinfunction "f20_f20") (pintype "bidirectional+no_connect"))
    )
    (net (code "231") (name "/HA20_N") (class "Default")
      (node (ref "J2") (pin "e19") (pinfunction "e19_e19") (pintype "bidirectional"))
    )
    (net (code "232") (name "/HA20_P") (class "Default")
      (node (ref "J2") (pin "e18") (pinfunction "e18_e18") (pintype "bidirectional"))
    )
    (net (code "233") (name "/HA21_N") (class "Default")
      (node (ref "J2") (pin "k20") (pinfunction "k20_k20") (pintype "bidirectional"))
    )
    (net (code "234") (name "/HA21_P") (class "Default")
      (node (ref "J2") (pin "k19") (pinfunction "k19_k19") (pintype "bidirectional"))
    )
    (net (code "235") (name "/HA23_N") (class "Default")
      (node (ref "B5") (pin "1") (pinfunction "1_1") (pintype "bidirectional"))
      (node (ref "J2") (pin "k23") (pinfunction "k23_k23") (pintype "bidirectional"))
    )
    (net (code "236") (name "/HA23_P") (class "Default")
      (node (ref "B1") (pin "1") (pinfunction "1_1") (pintype "bidirectional"))
      (node (ref "J2") (pin "k22") (pinfunction "k22_k22") (pintype "bidirectional"))
    )
    (net (code "237") (name "/INT_A_G_DRV1") (class "Default")
      (node (ref "J2") (pin "j21") (pinfunction "j21_j21") (pintype "bidirectional"))
    )
    (net (code "238") (name "/INT_A_G_DRV2") (class "Default")
      (node (ref "J2") (pin "j22") (pinfunction "j22_j22") (pintype "bidirectional"))
    )
    (net (code "240") (name "/INT_B_G_DRV1") (class "Default")
      (node (ref "J2") (pin "f23") (pinfunction "f23_f23") (pintype "bidirectional"))
    )
    (net (code "241") (name "/INT_B_G_DRV2") (class "Default")
      (node (ref "J2") (pin "e36") (pinfunction "e36_e36") (pintype "bidirectional"))
    )
    (net (code "243") (name "/LA03_N") (class "Default")
      (node (ref "J2") (pin "g10") (pinfunction "g10_g10") (pintype "bidirectional"))
    )
    (net (code "244") (name "/LA03_P") (class "Default")
      (node (ref "J2") (pin "g9") (pinfunction "g9_g9") (pintype "bidirectional"))
    )
    (net (code "245") (name "/OVERTEMPn") (class "Default")
      (node (ref "IC12") (pin "3") (pinfunction "O.S._3") (pintype "output"))
      (node (ref "R79") (pin "1") (pinfunction "1_1") (pintype "passive"))
    )
    (net (code "246") (name "/PG_M2C") (class "Default")
      (node (ref "J2") (pin "f1") (pinfunction "f1_f1") (pintype "bidirectional"))
    )
    (net (code "247") (name "/SCL") (class "Default")
      (node (ref "IC12") (pin "2") (pinfunction "SCL_2") (pintype "input"))
      (node (ref "IC13") (pin "6") (pinfunction "SCL_6") (pintype "input"))
      (node (ref "J2") (pin "c30") (pinfunction "c30_c30") (pintype "bidirectional"))
      (node (ref "R58") (pin "1") (pinfunction "1_1") (pintype "passive"))
    )
    (net (code "248") (name "/SDA") (class "Default")
      (node (ref "IC12") (pin "1") (pinfunction "SDA_1") (pintype "bidirectional"))
      (node (ref "IC13") (pin "5") (pinfunction "SDA_5") (pintype "bidirectional"))
      (node (ref "J2") (pin "c31") (pinfunction "c31_c31") (pintype "bidirectional"))
      (node (ref "R56") (pin "1") (pinfunction "1_1") (pintype "passive"))
    )
    (net (code "249") (name "/TDI") (class "Default")
      (node (ref "J2") (pin "d30") (pinfunction "d30_d30") (pintype "bidirectional"))
      (node (ref "J2") (pin "d31") (pinfunction "d31_d31") (pintype "bidirectional"))
    )
    (net (code "250") (name "/VREF_A_M2C") (class "Default")
      (node (ref "J2") (pin "h1") (pinfunction "h1_h1") (pintype "bidirectional+no_connect"))
    )
    (net (code "251") (name "3P3VAUX") (class "Default")
      (node (ref "C100") (pin "2") (pinfunction "2_2") (pintype "passive"))
      (node (ref "C99") (pin "2") (pinfunction "2_2") (pintype "passive"))
      (node (ref "IC12") (pin "8") (pinfunction "+VS_8") (pintype "power_in"))
      (node (ref "IC13") (pin "8") (pinfunction "VCC_8") (pintype "power_in"))
      (node (ref "J2") (pin "d32") (pinfunction "d32_d32") (pintype "bidirectional"))
      (node (ref "R56") (pin "2") (pinfunction "2_2") (pintype "passive"))
      (node (ref "R58") (pin "2") (pinfunction "2_2") (pintype "passive"))
      (node (ref "R79") (pin "2") (pinfunction "2_2") (pintype "passive"))
    )
    (net (code "252") (name "GND") (class "Default")
      (node (ref "B10") (pin "1") (pinfunction "1_1") (pintype "bidirectional"))
      (node (ref "B16") (pin "1") (pinfunction "1_1") (pintype "bidirectional"))
      (node (ref "B7") (pin "1") (pinfunction "1_1") (pintype "bidirectional"))
      (node (ref "B8") (pin "1") (pinfunction "1_1") (pintype "bidirectional"))
      (node (ref "B9") (pin "1") (pinfunction "1_1") (pintype "bidirectional"))
      (node (ref "C100") (pin "1") (pinfunction "1_1") (pintype "passive"))
      (node (ref "C99") (pin "1") (pinfunction "1_1") (pintype "passive"))
      (node (ref "IC12") (pin "4") (pinfunction "GND_4") (pintype "power_in"))
      (node (ref "IC12") (pin "5") (pinfunction "A2_5") (pintype "input"))
      (node (ref "IC12") (pin "6") (pinfunction "A1_6") (pintype "input"))
      (node (ref "IC12") (pin "7") (pinfunction "A0_7") (pintype "input"))
      (node (ref "IC13") (pin "3") (pinfunction "A2_3") (pintype "input"))
      (node (ref "IC13") (pin "4") (pinfunction "VSS_4") (pintype "power_in"))
      (node (ref "IC13") (pin "7") (pinfunction "WP_7") (pintype "input"))
      (node (ref "IC13") (pin "9") (pinfunction "EP_9") (pintype "power_in"))
      (node (ref "J2") (pin "a1") (pinfunction "a1_a1") (pintype "bidirectional"))
      (node (ref "J2") (pin "a12") (pinfunction "a12_a12") (pintype "bidirectional"))
      (node (ref "J2") (pin "a13") (pinfunction "a13_a13") (pintype "bidirectional"))
      (node (ref "J2") (pin "a16") (pinfunction "a16_a16") (pintype "bidirectional"))
      (node (ref "J2") (pin "a17") (pinfunction "a17_a17") (pintype "bidirectional"))
      (node (ref "J2") (pin "a20") (pinfunction "a20_a20") (pintype "bidirectional"))
      (node (ref "J2") (pin "a21") (pinfunction "a21_a21") (pintype "bidirectional"))
      (node (ref "J2") (pin "a24") (pinfunction "a24_a24") (pintype "bidirectional"))
      (node (ref "J2") (pin "a25") (pinfunction "a25_a25") (pintype "bidirectional"))
      (node (ref "J2") (pin "a28") (pinfunction "a28_a28") (pintype "bidirectional"))
      (node (ref "J2") (pin "a29") (pinfunction "a29_a29") (pintype "bidirectional"))
      (node (ref "J2") (pin "a32") (pinfunction "a32_a32") (pintype "bidirectional"))
      (node (ref "J2") (pin "a33") (pinfunction "a33_a33") (pintype "bidirectional"))
      (node (ref "J2") (pin "a36") (pinfunction "a36_a36") (pintype "bidirectional"))
      (node (ref "J2") (pin "a37") (pinfunction "a37_a37") (pintype "bidirectional"))
      (node (ref "J2") (pin "a4") (pinfunction "a4_a4") (pintype "bidirectional"))
      (node (ref "J2") (pin "a40") (pinfunction "a40_a40") (pintype "bidirectional"))
      (node (ref "J2") (pin "a5") (pinfunction "a5_a5") (pintype "bidirectional"))
      (node (ref "J2") (pin "a8") (pinfunction "a8_a8") (pintype "bidirectional"))
      (node (ref "J2") (pin "a9") (pinfunction "a9_a9") (pintype "bidirectional"))
      (node (ref "J2") (pin "b10") (pinfunction "b10_b10") (pintype "bidirectional"))
      (node (ref "J2") (pin "b11") (pinfunction "b11_b11") (pintype "bidirectional"))
      (node (ref "J2") (pin "b14") (pinfunction "b14_b14") (pintype "bidirectional"))
      (node (ref "J2") (pin "b15") (pinfunction "b15_b15") (pintype "bidirectional"))
      (node (ref "J2") (pin "b18") (pinfunction "b18_b18") (pintype "bidirectional"))
      (node (ref "J2") (pin "b19") (pinfunction "b19_b19") (pintype "bidirectional"))
      (node (ref "J2") (pin "b2") (pinfunction "b2_b2") (pintype "bidirectional"))
      (node (ref "J2") (pin "b22") (pinfunction "b22_b22") (pintype "bidirectional"))
      (node (ref "J2") (pin "b23") (pinfunction "b23_b23") (pintype "bidirectional"))
      (node (ref "J2") (pin "b26") (pinfunction "b26_b26") (pintype "bidirectional"))
      (node (ref "J2") (pin "b27") (pinfunction "b27_b27") (pintype "bidirectional"))
      (node (ref "J2") (pin "b3") (pinfunction "b3_b3") (pintype "bidirectional"))
      (node (ref "J2") (pin "b30") (pinfunction "b30_b30") (pintype "bidirectional"))
      (node (ref "J2") (pin "b31") (pinfunction "b31_b31") (pintype "bidirectional"))
      (node (ref "J2") (pin "b34") (pinfunction "b34_b34") (pintype "bidirectional"))
      (node (ref "J2") (pin "b35") (pinfunction "b35_b35") (pintype "bidirectional"))
      (node (ref "J2") (pin "b38") (pinfunction "b38_b38") (pintype "bidirectional"))
      (node (ref "J2") (pin "b39") (pinfunction "b39_b39") (pintype "bidirectional"))
      (node (ref "J2") (pin "b6") (pinfunction "b6_b6") (pintype "bidirectional"))
      (node (ref "J2") (pin "b7") (pinfunction "b7_b7") (pintype "bidirectional"))
      (node (ref "J2") (pin "c1") (pinfunction "c1_c1") (pintype "bidirectional"))
      (node (ref "J2") (pin "c12") (pinfunction "c12_c12") (pintype "bidirectional"))
      (node (ref "J2") (pin "c13") (pinfunction "c13_c13") (pintype "bidirectional"))
      (node (ref "J2") (pin "c16") (pinfunction "c16_c16") (pintype "bidirectional"))
      (node (ref "J2") (pin "c17") (pinfunction "c17_c17") (pintype "bidirectional"))
      (node (ref "J2") (pin "c20") (pinfunction "c20_c20") (pintype "bidirectional"))
      (node (ref "J2") (pin "c21") (pinfunction "c21_c21") (pintype "bidirectional"))
      (node (ref "J2") (pin "c24") (pinfunction "c24_c24") (pintype "bidirectional"))
      (node (ref "J2") (pin "c25") (pinfunction "c25_c25") (pintype "bidirectional"))
      (node (ref "J2") (pin "c28") (pinfunction "c28_c28") (pintype "bidirectional"))
      (node (ref "J2") (pin "c29") (pinfunction "c29_c29") (pintype "bidirectional"))
      (node (ref "J2") (pin "c32") (pinfunction "c32_c32") (pintype "bidirectional"))
      (node (ref "J2") (pin "c33") (pinfunction "c33_c33") (pintype "bidirectional"))
      (node (ref "J2") (pin "c36") (pinfunction "c36_c36") (pintype "bidirectional"))
      (node (ref "J2") (pin "c38") (pinfunction "c38_c38") (pintype "bidirectional"))
      (node (ref "J2") (pin "c4") (pinfunction "c4_c4") (pintype "bidirectional"))
      (node (ref "J2") (pin "c40") (pinfunction "c40_c40") (pintype "bidirectional"))
      (node (ref "J2") (pin "c5") (pinfunction "c5_c5") (pintype "bidirectional"))
      (node (ref "J2") (pin "c8") (pinfunction "c8_c8") (pintype "bidirectional"))
      (node (ref "J2") (pin "c9") (pinfunction "c9_c9") (pintype "bidirectional"))
      (node (ref "J2") (pin "d10") (pinfunction "d10_d10") (pintype "bidirectional"))
      (node (ref "J2") (pin "d13") (pinfunction "d13_d13") (pintype "bidirectional"))
      (node (ref "J2") (pin "d16") (pinfunction "d16_d16") (pintype "bidirectional"))
      (node (ref "J2") (pin "d19") (pinfunction "d19_d19") (pintype "bidirectional"))
      (node (ref "J2") (pin "d2") (pinfunction "d2_d2") (pintype "bidirectional"))
      (node (ref "J2") (pin "d22") (pinfunction "d22_d22") (pintype "bidirectional"))
      (node (ref "J2") (pin "d25") (pinfunction "d25_d25") (pintype "bidirectional"))
      (node (ref "J2") (pin "d28") (pinfunction "d28_d28") (pintype "bidirectional"))
      (node (ref "J2") (pin "d3") (pinfunction "d3_d3") (pintype "bidirectional"))
      (node (ref "J2") (pin "d37") (pinfunction "d37_d37") (pintype "bidirectional"))
      (node (ref "J2") (pin "d39") (pinfunction "d39_d39") (pintype "bidirectional"))
      (node (ref "J2") (pin "d6") (pinfunction "d6_d6") (pintype "bidirectional"))
      (node (ref "J2") (pin "d7") (pinfunction "d7_d7") (pintype "bidirectional"))
      (node (ref "J2") (pin "e1") (pinfunction "e1_e1") (pintype "bidirectional"))
      (node (ref "J2") (pin "e11") (pinfunction "e11_e11") (pintype "bidirectional"))
      (node (ref "J2") (pin "e14") (pinfunction "e14_e14") (pintype "bidirectional"))
      (node (ref "J2") (pin "e17") (pinfunction "e17_e17") (pintype "bidirectional"))
      (node (ref "J2") (pin "e20") (pinfunction "e20_e20") (pintype "bidirectional"))
      (node (ref "J2") (pin "e23") (pinfunction "e23_e23") (pintype "bidirectional"))
      (node (ref "J2") (pin "e26") (pinfunction "e26_e26") (pintype "bidirectional"))
      (node (ref "J2") (pin "e29") (pinfunction "e29_e29") (pintype "bidirectional"))
      (node (ref "J2") (pin "e32") (pinfunction "e32_e32") (pintype "bidirectional"))
      (node (ref "J2") (pin "e35") (pinfunction "e35_e35") (pintype "bidirectional"))
      (node (ref "J2") (pin "e38") (pinfunction "e38_e38") (pintype "bidirectional"))
      (node (ref "J2") (pin "e4") (pinfunction "e4_e4") (pintype "bidirectional"))
      (node (ref "J2") (pin "e40") (pinfunction "e40_e40") (pintype "bidirectional"))
      (node (ref "J2") (pin "e5") (pinfunction "e5_e5") (pintype "bidirectional"))
      (node (ref "J2") (pin "e8") (pinfunction "e8_e8") (pintype "bidirectional"))
      (node (ref "J2") (pin "f12") (pinfunction "f12_f12") (pintype "bidirectional"))
      (node (ref "J2") (pin "f15") (pinfunction "f15_f15") (pintype "bidirectional"))
      (node (ref "J2") (pin "f18") (pinfunction "f18_f18") (pintype "bidirectional"))
      (node (ref "J2") (pin "f2") (pinfunction "f2_f2") (pintype "bidirectional"))
      (node (ref "J2") (pin "f21") (pinfunction "f21_f21") (pintype "bidirectional"))
      (node (ref "J2") (pin "f24") (pinfunction "f24_f24") (pintype "bidirectional"))
      (node (ref "J2") (pin "f27") (pinfunction "f27_f27") (pintype "bidirectional"))
      (node (ref "J2") (pin "f3") (pinfunction "f3_f3") (pintype "bidirectional"))
      (node (ref "J2") (pin "f30") (pinfunction "f30_f30") (pintype "bidirectional"))
      (node (ref "J2") (pin "f33") (pinfunction "f33_f33") (pintype "bidirectional"))
      (node (ref "J2") (pin "f36") (pinfunction "f36_f36") (pintype "bidirectional"))
      (node (ref "J2") (pin "f39") (pinfunction "f39_f39") (pintype "bidirectional"))
      (node (ref "J2") (pin "f6") (pinfunction "f6_f6") (pintype "bidirectional"))
      (node (ref "J2") (pin "f9") (pinfunction "f9_f9") (pintype "bidirectional"))
      (node (ref "J2") (pin "g1") (pinfunction "g1_g1") (pintype "bidirectional"))
      (node (ref "J2") (pin "g11") (pinfunction "g11_g11") (pintype "bidirectional"))
      (node (ref "J2") (pin "g14") (pinfunction "g14_g14") (pintype "bidirectional"))
      (node (ref "J2") (pin "g17") (pinfunction "g17_g17") (pintype "bidirectional"))
      (node (ref "J2") (pin "g20") (pinfunction "g20_g20") (pintype "bidirectional"))
      (node (ref "J2") (pin "g23") (pinfunction "g23_g23") (pintype "bidirectional"))
      (node (ref "J2") (pin "g26") (pinfunction "g26_g26") (pintype "bidirectional"))
      (node (ref "J2") (pin "g29") (pinfunction "g29_g29") (pintype "bidirectional"))
      (node (ref "J2") (pin "g32") (pinfunction "g32_g32") (pintype "bidirectional"))
      (node (ref "J2") (pin "g35") (pinfunction "g35_g35") (pintype "bidirectional"))
      (node (ref "J2") (pin "g38") (pinfunction "g38_g38") (pintype "bidirectional"))
      (node (ref "J2") (pin "g4") (pinfunction "g4_g4") (pintype "bidirectional"))
      (node (ref "J2") (pin "g40") (pinfunction "g40_g40") (pintype "bidirectional"))
      (node (ref "J2") (pin "g5") (pinfunction "g5_g5") (pintype "bidirectional"))
      (node (ref "J2") (pin "g8") (pinfunction "g8_g8") (pintype "bidirectional"))
      (node (ref "J2") (pin "h12") (pinfunction "h12_h12") (pintype "bidirectional"))
      (node (ref "J2") (pin "h15") (pinfunction "h15_h15") (pintype "bidirectional"))
      (node (ref "J2") (pin "h18") (pinfunction "h18_h18") (pintype "bidirectional"))
      (node (ref "J2") (pin "h2") (pinfunction "h2_h2") (pintype "bidirectional"))
      (node (ref "J2") (pin "h21") (pinfunction "h21_h21") (pintype "bidirectional"))
      (node (ref "J2") (pin "h24") (pinfunction "h24_h24") (pintype "bidirectional"))
      (node (ref "J2") (pin "h27") (pinfunction "h27_h27") (pintype "bidirectional"))
      (node (ref "J2") (pin "h3") (pinfunction "h3_h3") (pintype "bidirectional"))
      (node (ref "J2") (pin "h30") (pinfunction "h30_h30") (pintype "bidirectional"))
      (node (ref "J2") (pin "h33") (pinfunction "h33_h33") (pintype "bidirectional"))
      (node (ref "J2") (pin "h36") (pinfunction "h36_h36") (pintype "bidirectional"))
      (node (ref "J2") (pin "h39") (pinfunction "h39_h39") (pintype "bidirectional"))
      (node (ref "J2") (pin "h6") (pinfunction "h6_h6") (pintype "bidirectional"))
      (node (ref "J2") (pin "h9") (pinfunction "h9_h9") (pintype "bidirectional"))
      (node (ref "J2") (pin "j1") (pinfunction "j1_j1") (pintype "bidirectional"))
      (node (ref "J2") (pin "j11") (pinfunction "j11_j11") (pintype "bidirectional"))
      (node (ref "J2") (pin "j14") (pinfunction "j14_j14") (pintype "bidirectional"))
      (node (ref "J2") (pin "j17") (pinfunction "j17_j17") (pintype "bidirectional"))
      (node (ref "J2") (pin "j20") (pinfunction "j20_j20") (pintype "bidirectional"))
      (node (ref "J2") (pin "j23") (pinfunction "j23_j23") (pintype "bidirectional"))
      (node (ref "J2") (pin "j26") (pinfunction "j26_j26") (pintype "bidirectional"))
      (node (ref "J2") (pin "j29") (pinfunction "j29_j29") (pintype "bidirectional"))
      (node (ref "J2") (pin "j32") (pinfunction "j32_j32") (pintype "bidirectional"))
      (node (ref "J2") (pin "j35") (pinfunction "j35_j35") (pintype "bidirectional"))
      (node (ref "J2") (pin "j38") (pinfunction "j38_j38") (pintype "bidirectional"))
      (node (ref "J2") (pin "j4") (pinfunction "j4_j4") (pintype "bidirectional"))
      (node (ref "J2") (pin "j40") (pinfunction "j40_j40") (pintype "bidirectional"))
      (node (ref "J2") (pin "j5") (pinfunction "j5_j5") (pintype "bidirectional"))
      (node (ref "J2") (pin "j8") (pinfunction "j8_j8") (pintype "bidirectional"))
      (node (ref "J2") (pin "k12") (pinfunction "k12_k12") (pintype "bidirectional"))
      (node (ref "J2") (pin "k15") (pinfunction "k15_k15") (pintype "bidirectional"))
      (node (ref "J2") (pin "k18") (pinfunction "k18_k18") (pintype "bidirectional"))
      (node (ref "J2") (pin "k2") (pinfunction "k2_k2") (pintype "bidirectional"))
      (node (ref "J2") (pin "k21") (pinfunction "k21_k21") (pintype "bidirectional"))
      (node (ref "J2") (pin "k24") (pinfunction "k24_k24") (pintype "bidirectional"))
      (node (ref "J2") (pin "k27") (pinfunction "k27_k27") (pintype "bidirectional"))
      (node (ref "J2") (pin "k3") (pinfunction "k3_k3") (pintype "bidirectional"))
      (node (ref "J2") (pin "k30") (pinfunction "k30_k30") (pintype "bidirectional"))
      (node (ref "J2") (pin "k33") (pinfunction "k33_k33") (pintype "bidirectional"))
      (node (ref "J2") (pin "k36") (pinfunction "k36_k36") (pintype "bidirectional"))
      (node (ref "J2") (pin "k39") (pinfunction "k39_k39") (pintype "bidirectional"))
      (node (ref "J2") (pin "k6") (pinfunction "k6_k6") (pintype "bidirectional"))
      (node (ref "J2") (pin "k9") (pinfunction "k9_k9") (pintype "bidirectional"))
    )
    (net (code "253") (name "P3V3_FMC") (class "Default")
      (node (ref "B15") (pin "1") (pinfunction "1_1") (pintype "bidirectional"))
      (node (ref "J2") (pin "c39") (pinfunction "c39_c39") (pintype "bidirectional"))
      (node (ref "J2") (pin "d36") (pinfunction "d36_d36") (pintype "bidirectional"))
      (node (ref "J2") (pin "d38") (pinfunction "d38_d38") (pintype "bidirectional"))
      (node (ref "J2") (pin "d40") (pinfunction "d40_d40") (pintype "bidirectional"))
      (node (ref "R38") (pin "1") (pinfunction "1_1") (pintype "passive"))
    )
    (net (code "254") (name "P12V0_FMC") (class "Default")
      (node (ref "B14") (pin "1") (pinfunction "1_1") (pintype "bidirectional"))
      (node (ref "J2") (pin "c35") (pinfunction "c35_c35") (pintype "bidirectional"))
      (node (ref "J2") (pin "c37") (pinfunction "c37_c37") (pintype "bidirectional"))
    )
    (net (code "255") (name "VADJ") (class "Default")
      (node (ref "B13") (pin "1") (pinfunction "1_1") (pintype "bidirectional"))
      (node (ref "J2") (pin "e39") (pinfunction "e39_e39") (pintype "bidirectional"))
      (node (ref "J2") (pin "f40") (pinfunction "f40_f40") (pintype "bidirectional"))
      (node (ref "J2") (pin "g39") (pinfunction "g39_g39") (pintype "bidirectional"))
      (node (ref "J2") (pin "h40") (pinfunction "h40_h40") (pintype "bidirectional"))
    )
    (net (code "256") (name "unconnected-(J2-Pada2)") (class "Default")
      (node (ref "J2") (pin "a2") (pinfunction "a2_a2") (pintype "bidirectional+no_connect"))
    )
    (net (code "257") (name "unconnected-(J2-Pada3)") (class "Default")
      (node (ref "J2") (pin "a3") (pinfunction "a3_a3") (pintype "bidirectional+no_connect"))
    )
    (net (code "258") (name "unconnected-(J2-Pada6)") (class "Default")
      (node (ref "J2") (pin "a6") (pinfunction "a6_a6") (pintype "bidirectional+no_connect"))
    )
    (net (code "259") (name "unconnected-(J2-Pada7)") (class "Default")
      (node (ref "J2") (pin "a7") (pinfunction "a7_a7") (pintype "bidirectional+no_connect"))
    )
    (net (code "260") (name "unconnected-(J2-Pada10)") (class "Default")
      (node (ref "J2") (pin "a10") (pinfunction "a10_a10") (pintype "bidirectional+no_connect"))
    )
    (net (code "261") (name "unconnected-(J2-Pada11)") (class "Default")
      (node (ref "J2") (pin "a11") (pinfunction "a11_a11") (pintype "bidirectional+no_connect"))
    )
    (net (code "262") (name "unconnected-(J2-Pada14)") (class "Default")
      (node (ref "J2") (pin "a14") (pinfunction "a14_a14") (pintype "bidirectional+no_connect"))
    )
    (net (code "263") (name "unconnected-(J2-Pada15)") (class "Default")
      (node (ref "J2") (pin "a15") (pinfunction "a15_a15") (pintype "bidirectional+no_connect"))
    )
    (net (code "264") (name "unconnected-(J2-Pada18)") (class "Default")
      (node (ref "J2") (pin "a18") (pinfunction "a18_a18") (pintype "bidirectional+no_connect"))
    )
    (net (code "265") (name "unconnected-(J2-Pada19)") (class "Default")
      (node (ref "J2") (pin "a19") (pinfunction "a19_a19") (pintype "bidirectional+no_connect"))
    )
    (net (code "266") (name "unconnected-(J2-Pada22)") (class "Default")
      (node (ref "J2") (pin "a22") (pinfunction "a22_a22") (pintype "bidirectional+no_connect"))
    )
    (net (code "267") (name "unconnected-(J2-Pada23)") (class "Default")
      (node (ref "J2") (pin "a23") (pinfunction "a23_a23") (pintype "bidirectional+no_connect"))
    )
    (net (code "268") (name "unconnected-(J2-Pada26)") (class "Default")
      (node (ref "J2") (pin "a26") (pinfunction "a26_a26") (pintype "bidirectional+no_connect"))
    )
    (net (code "269") (name "unconnected-(J2-Pada27)") (class "Default")
      (node (ref "J2") (pin "a27") (pinfunction "a27_a27") (pintype "bidirectional+no_connect"))
    )
    (net (code "270") (name "unconnected-(J2-Pada30)") (class "Default")
      (node (ref "J2") (pin "a30") (pinfunction "a30_a30") (pintype "bidirectional+no_connect"))
    )
    (net (code "271") (name "unconnected-(J2-Pada31)") (class "Default")
      (node (ref "J2") (pin "a31") (pinfunction "a31_a31") (pintype "bidirectional+no_connect"))
    )
    (net (code "272") (name "unconnected-(J2-Pada34)") (class "Default")
      (node (ref "J2") (pin "a34") (pinfunction "a34_a34") (pintype "bidirectional+no_connect"))
    )
    (net (code "273") (name "unconnected-(J2-Pada35)") (class "Default")
      (node (ref "J2") (pin "a35") (pinfunction "a35_a35") (pintype "bidirectional+no_connect"))
    )
    (net (code "274") (name "unconnected-(J2-Pada38)") (class "Default")
      (node (ref "J2") (pin "a38") (pinfunction "a38_a38") (pintype "bidirectional+no_connect"))
    )
    (net (code "275") (name "unconnected-(J2-Pada39)") (class "Default")
      (node (ref "J2") (pin "a39") (pinfunction "a39_a39") (pintype "bidirectional+no_connect"))
    )
    (net (code "276") (name "unconnected-(J2-Padb4)") (class "Default")
      (node (ref "J2") (pin "b4") (pinfunction "b4_b4") (pintype "bidirectional+no_connect"))
    )
    (net (code "277") (name "unconnected-(J2-Padb5)") (class "Default")
      (node (ref "J2") (pin "b5") (pinfunction "b5_b5") (pintype "bidirectional+no_connect"))
    )
    (net (code "278") (name "unconnected-(J2-Padb8)") (class "Default")
      (node (ref "J2") (pin "b8") (pinfunction "b8_b8") (pintype "bidirectional+no_connect"))
    )
    (net (code "279") (name "unconnected-(J2-Padb9)") (class "Default")
      (node (ref "J2") (pin "b9") (pinfunction "b9_b9") (pintype "bidirectional+no_connect"))
    )
    (net (code "280") (name "unconnected-(J2-Padb12)") (class "Default")
      (node (ref "J2") (pin "b12") (pinfunction "b12_b12") (pintype "bidirectional+no_connect"))
    )
    (net (code "281") (name "unconnected-(J2-Padb13)") (class "Default")
      (node (ref "J2") (pin "b13") (pinfunction "b13_b13") (pintype "bidirectional+no_connect"))
    )
    (net (code "282") (name "unconnected-(J2-Padb16)") (class "Default")
      (node (ref "J2") (pin "b16") (pinfunction "b16_b16") (pintype "bidirectional+no_connect"))
    )
    (net (code "283") (name "unconnected-(J2-Padb17)") (class "Default")
      (node (ref "J2") (pin "b17") (pinfunction "b17_b17") (pintype "bidirectional+no_connect"))
    )
    (net (code "284") (name "unconnected-(J2-Padb20)") (class "Default")
      (node (ref "J2") (pin "b20") (pinfunction "b20_b20") (pintype "bidirectional+no_connect"))
    )
    (net (code "285") (name "unconnected-(J2-Padb21)") (class "Default")
      (node (ref "J2") (pin "b21") (pinfunction "b21_b21") (pintype "bidirectional+no_connect"))
    )
    (net (code "286") (name "unconnected-(J2-Padb24)") (class "Default")
      (node (ref "J2") (pin "b24") (pinfunction "b24_b24") (pintype "bidirectional+no_connect"))
    )
    (net (code "287") (name "unconnected-(J2-Padb25)") (class "Default")
      (node (ref "J2") (pin "b25") (pinfunction "b25_b25") (pintype "bidirectional+no_connect"))
    )
    (net (code "288") (name "unconnected-(J2-Padb28)") (class "Default")
      (node (ref "J2") (pin "b28") (pinfunction "b28_b28") (pintype "bidirectional+no_connect"))
    )
    (net (code "289") (name "unconnected-(J2-Padb29)") (class "Default")
      (node (ref "J2") (pin "b29") (pinfunction "b29_b29") (pintype "bidirectional+no_connect"))
    )
    (net (code "290") (name "unconnected-(J2-Padb32)") (class "Default")
      (node (ref "J2") (pin "b32") (pinfunction "b32_b32") (pintype "bidirectional+no_connect"))
    )
    (net (code "291") (name "unconnected-(J2-Padb33)") (class "Default")
      (node (ref "J2") (pin "b33") (pinfunction "b33_b33") (pintype "bidirectional+no_connect"))
    )
    (net (code "292") (name "unconnected-(J2-Padb36)") (class "Default")
      (node (ref "J2") (pin "b36") (pinfunction "b36_b36") (pintype "bidirectional+no_connect"))
    )
    (net (code "293") (name "unconnected-(J2-Padb37)") (class "Default")
      (node (ref "J2") (pin "b37") (pinfunction "b37_b37") (pintype "bidirectional+no_connect"))
    )
    (net (code "294") (name "unconnected-(J2-Padb40)") (class "Default")
      (node (ref "J2") (pin "b40") (pinfunction "b40_b40") (pintype "bidirectional+no_connect"))
    )
    (net (code "295") (name "unconnected-(J2-Padc2)") (class "Default")
      (node (ref "J2") (pin "c2") (pinfunction "c2_c2") (pintype "bidirectional+no_connect"))
    )
    (net (code "296") (name "unconnected-(J2-Padc3)") (class "Default")
      (node (ref "J2") (pin "c3") (pinfunction "c3_c3") (pintype "bidirectional+no_connect"))
    )
    (net (code "297") (name "unconnected-(J2-Padc6)") (class "Default")
      (node (ref "J2") (pin "c6") (pinfunction "c6_c6") (pintype "bidirectional+no_connect"))
    )
    (net (code "298") (name "unconnected-(J2-Padc7)") (class "Default")
      (node (ref "J2") (pin "c7") (pinfunction "c7_c7") (pintype "bidirectional+no_connect"))
    )
    (net (code "299") (name "unconnected-(J2-Padd1)") (class "Default")
      (node (ref "J2") (pin "d1") (pinfunction "d1_d1") (pintype "bidirectional+no_connect"))
    )
    (net (code "300") (name "unconnected-(J2-Padd4)") (class "Default")
      (node (ref "J2") (pin "d4") (pinfunction "d4_d4") (pintype "bidirectional+no_connect"))
    )
    (net (code "301") (name "unconnected-(J2-Padd5)") (class "Default")
      (node (ref "J2") (pin "d5") (pinfunction "d5_d5") (pintype "bidirectional+no_connect"))
    )
    (net (code "302") (name "unconnected-(J2-Padd29)") (class "Default")
      (node (ref "J2") (pin "d29") (pinfunction "d29_d29") (pintype "bidirectional+no_connect"))
    )
    (net (code "303") (name "unconnected-(J2-Padd33)") (class "Default")
      (node (ref "J2") (pin "d33") (pinfunction "d33_d33") (pintype "bidirectional+no_connect"))
    )
    (net (code "304") (name "unconnected-(J2-Padd34)") (class "Default")
      (node (ref "J2") (pin "d34") (pinfunction "d34_d34") (pintype "bidirectional+no_connect"))
    )
    (net (code "305") (name "unconnected-(J2-Padj39)") (class "Default")
      (node (ref "J2") (pin "j39") (pinfunction "j39_j39") (pintype "bidirectional"))
    )
    (net (code "306") (name "unconnected-(J2-Padk1)") (class "Default")
      (node (ref "J2") (pin "k1") (pinfunction "k1_k1") (pintype "bidirectional+no_connect"))
    )
    (net (code "307") (name "unconnected-(J2-Padk40)") (class "Default")
      (node (ref "J2") (pin "k40") (pinfunction "k40_k40") (pintype "bidirectional"))
    )
  )
)
